# riffleito-xbee.net
KiCad netlist of a schematic drawn in EAGLE
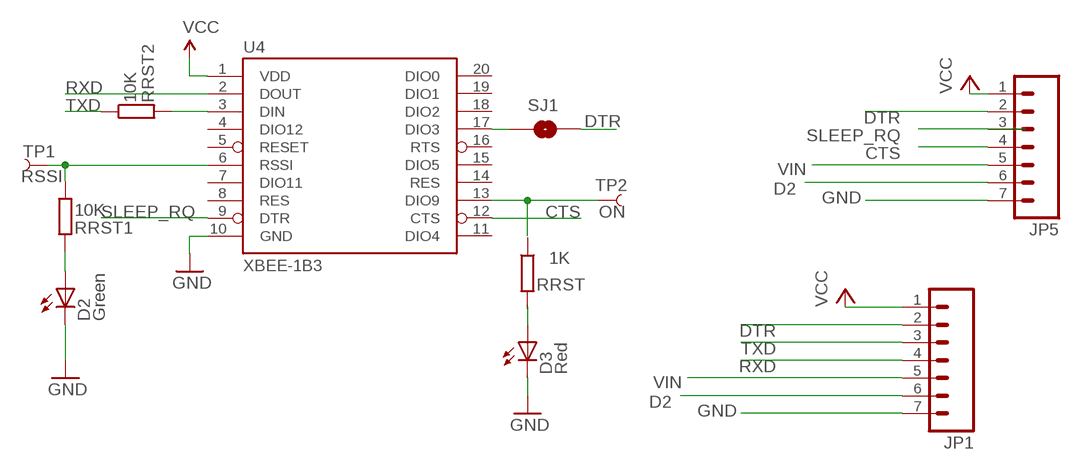
[diagram p0: schematic, sheet 1]

(export (version "E")
  (design (tool "Eeschema 10.0.6"))
  (components
    (comp (ref "D2")
      (value "Green")
      (footprint "eagle-import:LED-0603")
      (libsource (lib "eagle-import") (part "LED0603"))
    )
    (comp (ref "D3")
      (value "Red")
      (footprint "eagle-import:LED-0603")
      (libsource (lib "eagle-import") (part "LED0603"))
    )
    (comp (ref "JP1")
      (value "M07")
      (footprint "eagle-import:1X07")
      (libsource (lib "eagle-import") (part "M07"))
    )
    (comp (ref "JP5")
      (value "M07")
      (footprint "eagle-import:1X07")
      (libsource (lib "eagle-import") (part "M07"))
    )
    (comp (ref "RRST")
      (value "1K")
      (footprint "eagle-import:R0805")
      (libsource (lib "eagle-import") (part "R-EU_R0805"))
    )
    (comp (ref "RRST1")
      (value "10K")
      (footprint "eagle-import:R0805")
      (libsource (lib "eagle-import") (part "R-EU_R0805"))
    )
    (comp (ref "RRST2")
      (value "10K")
      (footprint "eagle-import:R0805")
      (libsource (lib "eagle-import") (part "R-EU_R0805"))
    )
    (comp (ref "SJ1")
      (value "SOLDERJUMPERNC")
      (footprint "eagle-import:SJ_2S")
      (libsource (lib "eagle-import") (part "SOLDERJUMPERNC"))
    )
    (comp (ref "TP1")
      (value "RSSI")
      (footprint "eagle-import:PAD.03X.05")
      (libsource (lib "eagle-import") (part "TEST-POINT3X5"))
    )
    (comp (ref "TP2")
      (value "ON")
      (footprint "eagle-import:PAD.03X.05")
      (libsource (lib "eagle-import") (part "TEST-POINT3X5"))
    )
    (comp (ref "U4")
      (value "XBEE-1B3")
      (footprint "eagle-import:XBEE-SMD")
      (libsource (lib "eagle-import") (part "XBEE-1B3"))
    )
  )
  (nets
    (net (code "1") (name "/CTS") (class "Default")
      (node (ref "JP5") (pin "4") (pinfunction "4_4") (pintype "passive"))
      (node (ref "U4") (pin "12") (pinfunction "CTS_12") (pintype "output"))
    )
    (net (code "2") (name "/D2") (class "Default")
      (node (ref "JP1") (pin "6") (pinfunction "6_6") (pintype "passive"))
      (node (ref "JP5") (pin "6") (pinfunction "6_6") (pintype "passive"))
    )
    (net (code "3") (name "/DTR") (class "Default")
      (node (ref "JP1") (pin "2") (pinfunction "2_2") (pintype "passive"))
      (node (ref "JP5") (pin "2") (pinfunction "2_2") (pintype "passive"))
      (node (ref "SJ1") (pin "2") (pinfunction "2_2") (pintype "passive"))
    )
    (net (code "4") (name "/RXD") (class "Default")
      (node (ref "JP1") (pin "4") (pinfunction "4_4") (pintype "passive"))
      (node (ref "U4") (pin "2") (pinfunction "DOUT_2") (pintype "output"))
    )
    (net (code "5") (name "/SLEEP_RQ") (class "Default")
      (node (ref "JP5") (pin "3") (pinfunction "3_3") (pintype "passive"))
      (node (ref "U4") (pin "9") (pinfunction "DTR_9") (pintype "bidirectional"))
    )
    (net (code "6") (name "/TXD") (class "Default")
      (node (ref "JP1") (pin "3") (pinfunction "3_3") (pintype "passive"))
      (node (ref "RRST2") (pin "1") (pinfunction "1_1") (pintype "passive"))
    )
    (net (code "7") (name "/VIN") (class "Default")
      (node (ref "JP1") (pin "5") (pinfunction "5_5") (pintype "passive"))
      (node (ref "JP5") (pin "5") (pinfunction "5_5") (pintype "passive"))
    )
    (net (code "8") (name "GND") (class "Default")
      (node (ref "D2") (pin "C") (pinfunction "C_C") (pintype "passive"))
      (node (ref "D3") (pin "C") (pinfunction "C_C") (pintype "passive"))
      (node (ref "JP1") (pin "7") (pinfunction "7_7") (pintype "passive"))
      (node (ref "JP5") (pin "7") (pinfunction "7_7") (pintype "passive"))
      (node (ref "U4") (pin "10") (pinfunction "GND_10") (pintype "power_in"))
    )
    (net (code "9") (name "Net-(D2-PadA)") (class "Default")
      (node (ref "D2") (pin "A") (pinfunction "A_A") (pintype "passive"))
      (node (ref "RRST1") (pin "2") (pinfunction "2_2") (pintype "passive"))
    )
    (net (code "10") (name "Net-(D3-PadA)") (class "Default")
      (node (ref "D3") (pin "A") (pinfunction "A_A") (pintype "passive"))
      (node (ref "RRST") (pin "2") (pinfunction "2_2") (pintype "passive"))
    )
    (net (code "11") (name "Net-(TP1-1)") (class "Default")
      (node (ref "RRST1") (pin "1") (pinfunction "1_1") (pintype "passive"))
      (node (ref "TP1") (pin "P$1") (pinfunction "1_P$1") (pintype "bidirectional"))
      (node (ref "U4") (pin "6") (pinfunction "RSSI_6") (pintype "bidirectional"))
    )
    (net (code "12") (name "Net-(TP2-1)") (class "Default")
      (node (ref "TP2") (pin "P$1") (pinfunction "1_P$1") (pintype "bidirectional"))
      (node (ref "U4") (pin "13") (pinfunction "DIO9_13") (pintype "bidirectional"))
    )
    (net (code "13") (name "Net-(U4-DIN)") (class "Default")
      (node (ref "RRST2") (pin "2") (pinfunction "2_2") (pintype "passive"))
      (node (ref "U4") (pin "3") (pinfunction "DIN_3") (pintype "input"))
    )
    (net (code "14") (name "Net-(U4-DIO3)") (class "Default")
      (node (ref "SJ1") (pin "1") (pinfunction "1_1") (pintype "passive"))
      (node (ref "U4") (pin "17") (pinfunction "DIO3_17") (pintype "bidirectional"))
    )
    (net (code "15") (name "VCC") (class "Default")
      (node (ref "JP1") (pin "1") (pinfunction "1_1") (pintype "passive"))
      (node (ref "JP5") (pin "1") (pinfunction "1_1") (pintype "passive"))
      (node (ref "U4") (pin "1") (pinfunction "VDD_1") (pintype "power_in"))
    )
    (net (code "16") (name "unconnected-(RRST-Pad1)") (class "Default")
      (node (ref "RRST") (pin "1") (pinfunction "1_1") (pintype "passive"))
    )
    (net (code "17") (name "unconnected-(U4-DIO0-Pad20)") (class "Default")
      (node (ref "U4") (pin "20") (pinfunction "DIO0_20") (pintype "bidirectional"))
    )
    (net (code "18") (name "unconnected-(U4-DIO1-Pad19)") (class "Default")
      (node (ref "U4") (pin "19") (pinfunction "DIO1_19") (pintype "bidirectional"))
    )
    (net (code "19") (name "unconnected-(U4-DIO2-Pad18)") (class "Default")
      (node (ref "U4") (pin "18") (pinfunction "DIO2_18") (pintype "bidirectional"))
    )
    (net (code "20") (name "unconnected-(U4-DIO4-Pad11)") (class "Default")
      (node (ref "U4") (pin "11") (pinfunction "DIO4_11") (pintype "bidirectional"))
    )
    (net (code "21") (name "unconnected-(U4-DIO5-Pad15)") (class "Default")
      (node (ref "U4") (pin "15") (pinfunction "DIO5_15") (pintype "bidirectional"))
    )
    (net (code "22") (name "unconnected-(U4-DIO11-Pad7)") (class "Default")
      (node (ref "U4") (pin "7") (pinfunction "DIO11_7") (pintype "bidirectional"))
    )
    (net (code "23") (name "unconnected-(U4-DIO12-Pad4)") (class "Default")
      (node (ref "U4") (pin "4") (pinfunction "DIO12_4") (pintype "bidirectional"))
    )
    (net (code "24") (name "unconnected-(U4-RES-Pad8)") (class "Default")
      (node (ref "U4") (pin "8") (pinfunction "RES_8") (pintype "bidirectional"))
    )
    (net (code "25") (name "unconnected-(U4-RES-Pad14)") (class "Default")
      (node (ref "U4") (pin "14") (pinfunction "RES_14") (pintype "bidirectional"))
    )
    (net (code "26") (name "unconnected-(U4-RESET-Pad5)") (class "Default")
      (node (ref "U4") (pin "5") (pinfunction "RESET_5") (pintype "input"))
    )
    (net (code "27") (name "unconnected-(U4-RTS-Pad16)") (class "Default")
      (node (ref "U4") (pin "16") (pinfunction "RTS_16") (pintype "input"))
    )
  )
)
